# digispark_adns2620.net
KiCad netlist of a schematic drawn in EAGLE
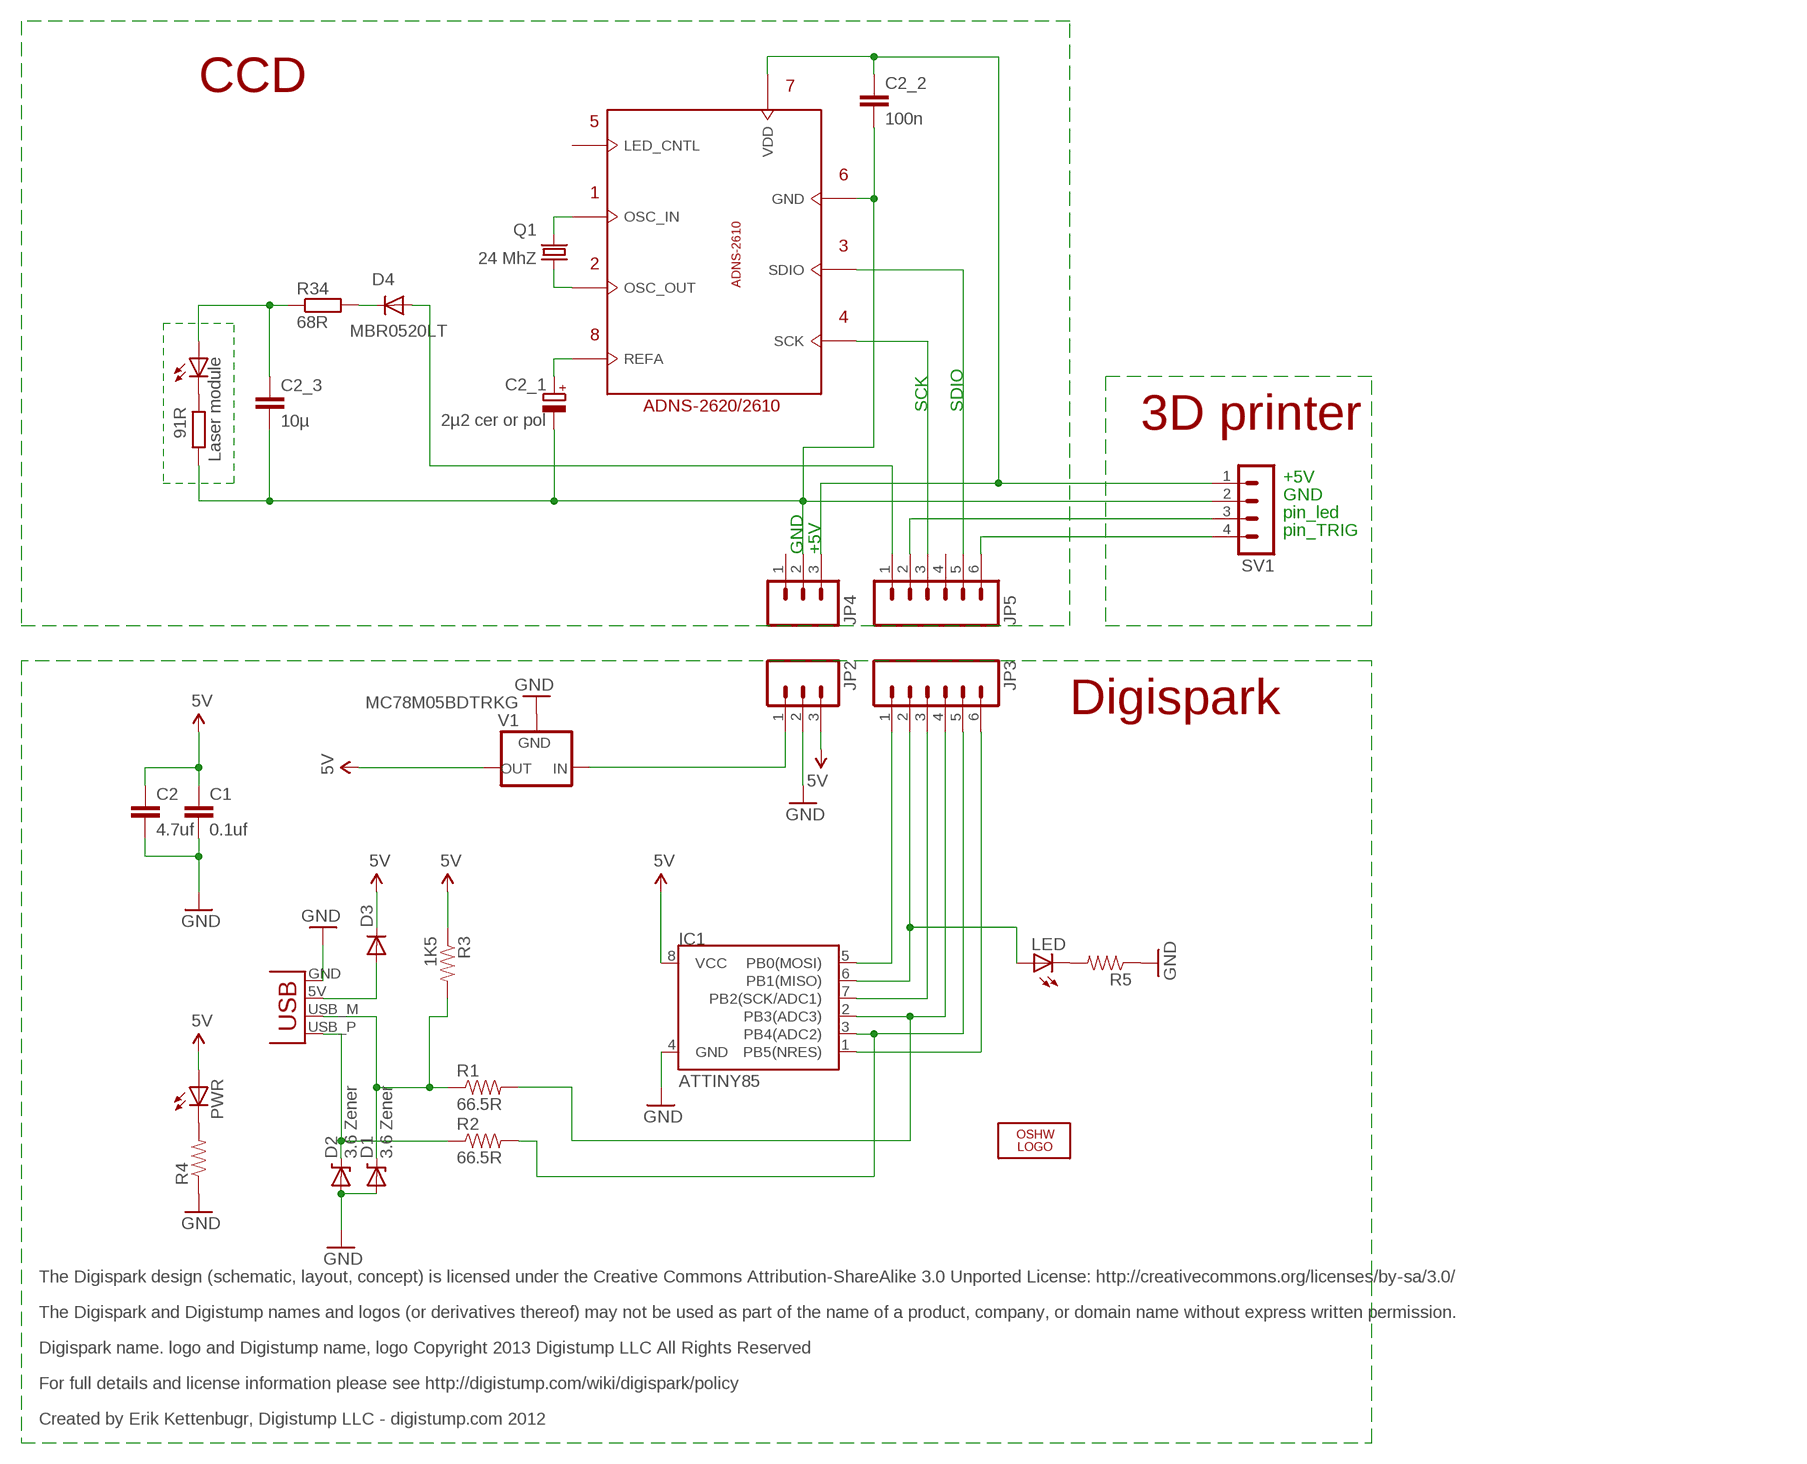
[diagram p0: schematic, sheet 1]

(export (version "E")
  (design (tool "Eeschema 10.0.6"))
  (components
    (comp (ref "C1")
      (value "0.1uf")
      (footprint "eagle-import:0402-CAP")
      (libsource (lib "eagle-import") (part "CAP0402-CAP"))
    )
    (comp (ref "C2")
      (value "4.7uf")
      (footprint "eagle-import:0805")
      (libsource (lib "eagle-import") (part "CAP0805"))
    )
    (comp (ref "C2_1")
      (value "2µ2 cer or pol")
      (footprint "eagle-import:CT3216")
      (libsource (lib "eagle-import") (part "CPOL-EUCT3216"))
    )
    (comp (ref "C2_2")
      (value "100n")
      (footprint "eagle-import:C0805K")
      (libsource (lib "eagle-import") (part "C-EUC0805K"))
    )
    (comp (ref "C2_3")
      (value "10µ")
      (footprint "eagle-import:C0805K")
      (libsource (lib "eagle-import") (part "C-EUC0805K"))
    )
    (comp (ref "D1")
      (value "3.6 Zener")
      (footprint "eagle-import:SOD-323")
      (libsource (lib "eagle-import") (part "DIODE-ZENER-BZT52"))
    )
    (comp (ref "D2")
      (value "3.6 Zener")
      (footprint "eagle-import:SOD-323")
      (libsource (lib "eagle-import") (part "DIODE-ZENER-BZT52"))
    )
    (comp (ref "D3")
      (value "MBR0520LT")
      (footprint "eagle-import:SOD123")
      (libsource (lib "eagle-import") (part "MBR0520LT"))
    )
    (comp (ref "D4")
      (value "MBR0520LT")
      (footprint "eagle-import:SOD123")
      (libsource (lib "eagle-import") (part "MBR0520LT"))
    )
    (comp (ref "IC1")
      (value "ATTINY85")
      (footprint "eagle-import:SO08-EIAJ")
      (libsource (lib "eagle-import") (part "ATTINY45"))
    )
    (comp (ref "IC2")
      (value "ADNS-2620/2610")
      (footprint "eagle-import:DIP-8_(GORA)")
      (libsource (lib "eagle-import") (part "ANDS-2610DIP-8_(GORA)"))
    )
    (comp (ref "JP2")
      (value "M03PTH")
      (footprint "eagle-import:1X03")
      (libsource (lib "eagle-import") (part "M03PTH"))
    )
    (comp (ref "JP3")
      (value "M06SIP")
      (footprint "eagle-import:1X06")
      (libsource (lib "eagle-import") (part "M06SIP"))
    )
    (comp (ref "JP4")
      (value "M03PTH")
      (footprint "eagle-import:1X03")
      (libsource (lib "eagle-import") (part "M03PTH"))
    )
    (comp (ref "JP5")
      (value "M06SIP")
      (footprint "eagle-import:1X06")
      (libsource (lib "eagle-import") (part "M06SIP"))
    )
    (comp (ref "LED")
      (value "LED0603")
      (footprint "eagle-import:LED-0603")
      (libsource (lib "eagle-import") (part "LED0603"))
    )
    (comp (ref "LED1")
      (value "Laser module")
      (footprint "eagle-import:LED5MM")
      (libsource (lib "eagle-import") (part "led_LED5MM"))
    )
    (comp (ref "LOGO2")
      (value "LOGO-OSHW-10MILX0200-NT")
      (footprint "eagle-import:OSHW_10X200_NOTEXT")
      (libsource (lib "eagle-import") (part "LOGO-OSHW-10MILX0200-NT"))
    )
    (comp (ref "PWR")
      (value "LED0603")
      (footprint "eagle-import:LED-0603")
      (libsource (lib "eagle-import") (part "LED0603"))
    )
    (comp (ref "Q1")
      (value "24 MhZ")
      (footprint "eagle-import:HC49_S")
      (libsource (lib "eagle-import") (part "CRYTALHC49S"))
    )
    (comp (ref "R1")
      (value "66.5R")
      (footprint "eagle-import:0402-RES")
      (libsource (lib "eagle-import") (part "RESISTOR0402-RES"))
    )
    (comp (ref "R2")
      (value "66.5R")
      (footprint "eagle-import:0402-RES")
      (libsource (lib "eagle-import") (part "RESISTOR0402-RES"))
    )
    (comp (ref "R3")
      (value "1K5")
      (footprint "eagle-import:0402-RES")
      (libsource (lib "eagle-import") (part "RESISTOR0402-RES"))
    )
    (comp (ref "R4")
      (value "RESISTOR0402-RES")
      (footprint "eagle-import:0402-RES")
      (libsource (lib "eagle-import") (part "RESISTOR0402-RES"))
    )
    (comp (ref "R5")
      (value "RESISTOR0402-RES")
      (footprint "eagle-import:0402-RES")
      (libsource (lib "eagle-import") (part "RESISTOR0402-RES"))
    )
    (comp (ref "R23")
      (value "91R")
      (footprint "eagle-import:R1206")
      (libsource (lib "eagle-import") (part "R-EU_R1206"))
    )
    (comp (ref "R34")
      (value "68R")
      (footprint "eagle-import:R0805")
      (libsource (lib "eagle-import") (part "R-EU_R0805"))
    )
    (comp (ref "SV1")
      (value "MA04-1")
      (footprint "eagle-import:MA04-1")
      (libsource (lib "eagle-import") (part "MA04-1"))
    )
    (comp (ref "V1")
      (value "MC78M05BDTRKG")
      (footprint "eagle-import:DPACK")
      (libsource (lib "eagle-import") (part "LP2950?CDT-3.0"))
    )
    (comp (ref "X1")
      (value "USBPCB")
      (footprint "eagle-import:USB-A-PCB")
      (libsource (lib "eagle-import") (part "USBPCB"))
    )
  )
  (nets
    (net (code "1") (name "5V") (class "Default")
      (node (ref "C1") (pin "1") (pinfunction "1_1") (pintype "passive"))
      (node (ref "C2") (pin "1") (pinfunction "1_1") (pintype "passive"))
      (node (ref "D3") (pin "C") (pinfunction "C_C") (pintype "passive"))
      (node (ref "IC1") (pin "8") (pinfunction "VCC_8") (pintype "bidirectional"))
      (node (ref "JP2") (pin "3") (pinfunction "3_3") (pintype "passive"))
      (node (ref "PWR") (pin "A") (pinfunction "A_A") (pintype "passive"))
      (node (ref "R3") (pin "1") (pinfunction "1_1") (pintype "passive"))
      (node (ref "V1") (pin "3") (pinfunction "OUT_3") (pintype "passive"))
    )
    (net (code "2") (name "GND") (class "Default")
      (node (ref "C1") (pin "2") (pinfunction "2_2") (pintype "passive"))
      (node (ref "C2") (pin "2") (pinfunction "2_2") (pintype "passive"))
      (node (ref "C2_1") (pin "-") (pinfunction "-_-") (pintype "passive"))
      (node (ref "C2_2") (pin "2") (pinfunction "2_2") (pintype "passive"))
      (node (ref "C2_3") (pin "2") (pinfunction "2_2") (pintype "passive"))
      (node (ref "D1") (pin "2") (pinfunction "A_2") (pintype "passive"))
      (node (ref "D2") (pin "2") (pinfunction "A_2") (pintype "passive"))
      (node (ref "IC1") (pin "4") (pinfunction "GND_4") (pintype "bidirectional"))
      (node (ref "IC2") (pin "6") (pinfunction "GND_6") (pintype "power_in"))
      (node (ref "JP2") (pin "2") (pinfunction "2_2") (pintype "passive"))
      (node (ref "JP4") (pin "2") (pinfunction "2_2") (pintype "passive"))
      (node (ref "R23") (pin "1") (pinfunction "1_1") (pintype "passive"))
      (node (ref "R4") (pin "1") (pinfunction "1_1") (pintype "passive"))
      (node (ref "R5") (pin "1") (pinfunction "1_1") (pintype "passive"))
      (node (ref "SV1") (pin "2") (pinfunction "2_2") (pintype "passive"))
      (node (ref "V1") (pin "4") (pinfunction "GND_4") (pintype "input"))
      (node (ref "X1") (pin "GND") (pinfunction "GND_GND") (pintype "bidirectional"))
    )
    (net (code "3") (name "Net-(C2_3-Pad1)") (class "Default")
      (node (ref "C2_3") (pin "1") (pinfunction "1_1") (pintype "passive"))
      (node (ref "LED1") (pin "A") (pinfunction "A_A") (pintype "passive"))
      (node (ref "R34") (pin "1") (pinfunction "1_1") (pintype "passive"))
    )
    (net (code "4") (name "Net-(D1-C)") (class "Default")
      (node (ref "D1") (pin "1") (pinfunction "C_1") (pintype "passive"))
      (node (ref "R1") (pin "1") (pinfunction "1_1") (pintype "passive"))
      (node (ref "R3") (pin "2") (pinfunction "2_2") (pintype "passive"))
      (node (ref "X1") (pin "USB_M") (pinfunction "D-_USB_M") (pintype "bidirectional"))
    )
    (net (code "5") (name "Net-(D2-C)") (class "Default")
      (node (ref "D2") (pin "1") (pinfunction "C_1") (pintype "passive"))
      (node (ref "R2") (pin "1") (pinfunction "1_1") (pintype "passive"))
      (node (ref "X1") (pin "USB_P") (pinfunction "D+_USB_P") (pintype "bidirectional"))
    )
    (net (code "6") (name "Net-(D4-PadA)") (class "Default")
      (node (ref "D4") (pin "A") (pinfunction "A_A") (pintype "passive"))
      (node (ref "JP5") (pin "1") (pinfunction "1_1") (pintype "passive"))
    )
    (net (code "7") (name "Net-(D4-PadC)") (class "Default")
      (node (ref "D4") (pin "C") (pinfunction "C_C") (pintype "passive"))
      (node (ref "R34") (pin "2") (pinfunction "2_2") (pintype "passive"))
    )
    (net (code "8") (name "Net-(IC1-PB0(MOSI))") (class "Default")
      (node (ref "IC1") (pin "5") (pinfunction "PB0(MOSI)_5") (pintype "bidirectional"))
      (node (ref "JP3") (pin "1") (pinfunction "1_1") (pintype "passive"))
    )
    (net (code "9") (name "Net-(IC1-PB1(MISO))") (class "Default")
      (node (ref "IC1") (pin "6") (pinfunction "PB1(MISO)_6") (pintype "bidirectional"))
      (node (ref "JP3") (pin "2") (pinfunction "2_2") (pintype "passive"))
      (node (ref "LED") (pin "A") (pinfunction "A_A") (pintype "passive"))
    )
    (net (code "10") (name "Net-(IC1-PB2(SCK{slash}ADC1))") (class "Default")
      (node (ref "IC1") (pin "7") (pinfunction "PB2(SCK/ADC1)_7") (pintype "bidirectional"))
      (node (ref "JP3") (pin "3") (pinfunction "3_3") (pintype "passive"))
    )
    (net (code "11") (name "Net-(IC1-PB3(ADC3))") (class "Default")
      (node (ref "IC1") (pin "2") (pinfunction "PB3(ADC3)_2") (pintype "bidirectional"))
      (node (ref "JP3") (pin "4") (pinfunction "4_4") (pintype "passive"))
      (node (ref "R1") (pin "2") (pinfunction "2_2") (pintype "passive"))
    )
    (net (code "12") (name "Net-(IC1-PB4(ADC2))") (class "Default")
      (node (ref "IC1") (pin "3") (pinfunction "PB4(ADC2)_3") (pintype "bidirectional"))
      (node (ref "JP3") (pin "5") (pinfunction "5_5") (pintype "passive"))
      (node (ref "R2") (pin "2") (pinfunction "2_2") (pintype "passive"))
    )
    (net (code "13") (name "Net-(IC1-PB5(NRES))") (class "Default")
      (node (ref "IC1") (pin "1") (pinfunction "PB5(NRES)_1") (pintype "bidirectional"))
      (node (ref "JP3") (pin "6") (pinfunction "6_6") (pintype "passive"))
    )
    (net (code "14") (name "Net-(IC2-OSC_IN)") (class "Default")
      (node (ref "IC2") (pin "1") (pinfunction "OSC_IN_1") (pintype "output"))
      (node (ref "Q1") (pin "2") (pinfunction "2_2") (pintype "passive"))
    )
    (net (code "15") (name "Net-(IC2-OSC_OUT)") (class "Default")
      (node (ref "IC2") (pin "2") (pinfunction "OSC_OUT_2") (pintype "input"))
      (node (ref "Q1") (pin "1") (pinfunction "1_1") (pintype "passive"))
    )
    (net (code "16") (name "Net-(IC2-REFA)") (class "Default")
      (node (ref "C2_1") (pin "+") (pinfunction "+_+") (pintype "passive"))
      (node (ref "IC2") (pin "8") (pinfunction "REFA_8") (pintype "open_collector"))
    )
    (net (code "17") (name "Net-(IC2-SCK)") (class "Default")
      (node (ref "IC2") (pin "4") (pinfunction "SCK_4") (pintype "bidirectional"))
      (node (ref "JP5") (pin "3") (pinfunction "3_3") (pintype "passive"))
    )
    (net (code "18") (name "Net-(IC2-SDIO)") (class "Default")
      (node (ref "IC2") (pin "3") (pinfunction "SDIO_3") (pintype "bidirectional"))
      (node (ref "JP5") (pin "5") (pinfunction "5_5") (pintype "passive"))
    )
    (net (code "19") (name "Net-(IC2-VDD)") (class "Default")
      (node (ref "C2_2") (pin "1") (pinfunction "1_1") (pintype "passive"))
      (node (ref "IC2") (pin "7") (pinfunction "VDD_7") (pintype "power_in"))
      (node (ref "JP4") (pin "3") (pinfunction "3_3") (pintype "passive"))
      (node (ref "SV1") (pin "1") (pinfunction "1_1") (pintype "passive"))
    )
    (net (code "20") (name "Net-(JP5-Pad2)") (class "Default")
      (node (ref "JP5") (pin "2") (pinfunction "2_2") (pintype "passive"))
      (node (ref "SV1") (pin "3") (pinfunction "3_3") (pintype "passive"))
    )
    (net (code "21") (name "Net-(JP5-Pad6)") (class "Default")
      (node (ref "JP5") (pin "6") (pinfunction "6_6") (pintype "passive"))
      (node (ref "SV1") (pin "4") (pinfunction "4_4") (pintype "passive"))
    )
    (net (code "22") (name "Net-(LED-PadC)") (class "Default")
      (node (ref "LED") (pin "C") (pinfunction "C_C") (pintype "passive"))
      (node (ref "R5") (pin "2") (pinfunction "2_2") (pintype "passive"))
    )
    (net (code "23") (name "Net-(LED1-C)") (class "Default")
      (node (ref "LED1") (pin "K") (pinfunction "C_K") (pintype "passive"))
      (node (ref "R23") (pin "2") (pinfunction "2_2") (pintype "passive"))
    )
    (net (code "24") (name "Net-(PWR-PadC)") (class "Default")
      (node (ref "PWR") (pin "C") (pinfunction "C_C") (pintype "passive"))
      (node (ref "R4") (pin "2") (pinfunction "2_2") (pintype "passive"))
    )
    (net (code "25") (name "Net-(V1-IN)") (class "Default")
      (node (ref "JP2") (pin "1") (pinfunction "1_1") (pintype "passive"))
      (node (ref "V1") (pin "1") (pinfunction "IN_1") (pintype "input"))
    )
    (net (code "26") (name "Net-(X1-VBUS)") (class "Default")
      (node (ref "D3") (pin "A") (pinfunction "A_A") (pintype "passive"))
      (node (ref "X1") (pin "5V") (pinfunction "VBUS_5V") (pintype "bidirectional"))
    )
    (net (code "27") (name "unconnected-(IC2-LED_CNTL-Pad5)") (class "Default")
      (node (ref "IC2") (pin "5") (pinfunction "LED_CNTL_5") (pintype "passive"))
    )
    (net (code "28") (name "unconnected-(JP4-Pad1)") (class "Default")
      (node (ref "JP4") (pin "1") (pinfunction "1_1") (pintype "passive"))
    )
    (net (code "29") (name "unconnected-(JP5-Pad4)") (class "Default")
      (node (ref "JP5") (pin "4") (pinfunction "4_4") (pintype "passive"))
    )
  )
)
